# WIFIAdapter.net
KiCad netlist of a schematic drawn in EAGLE
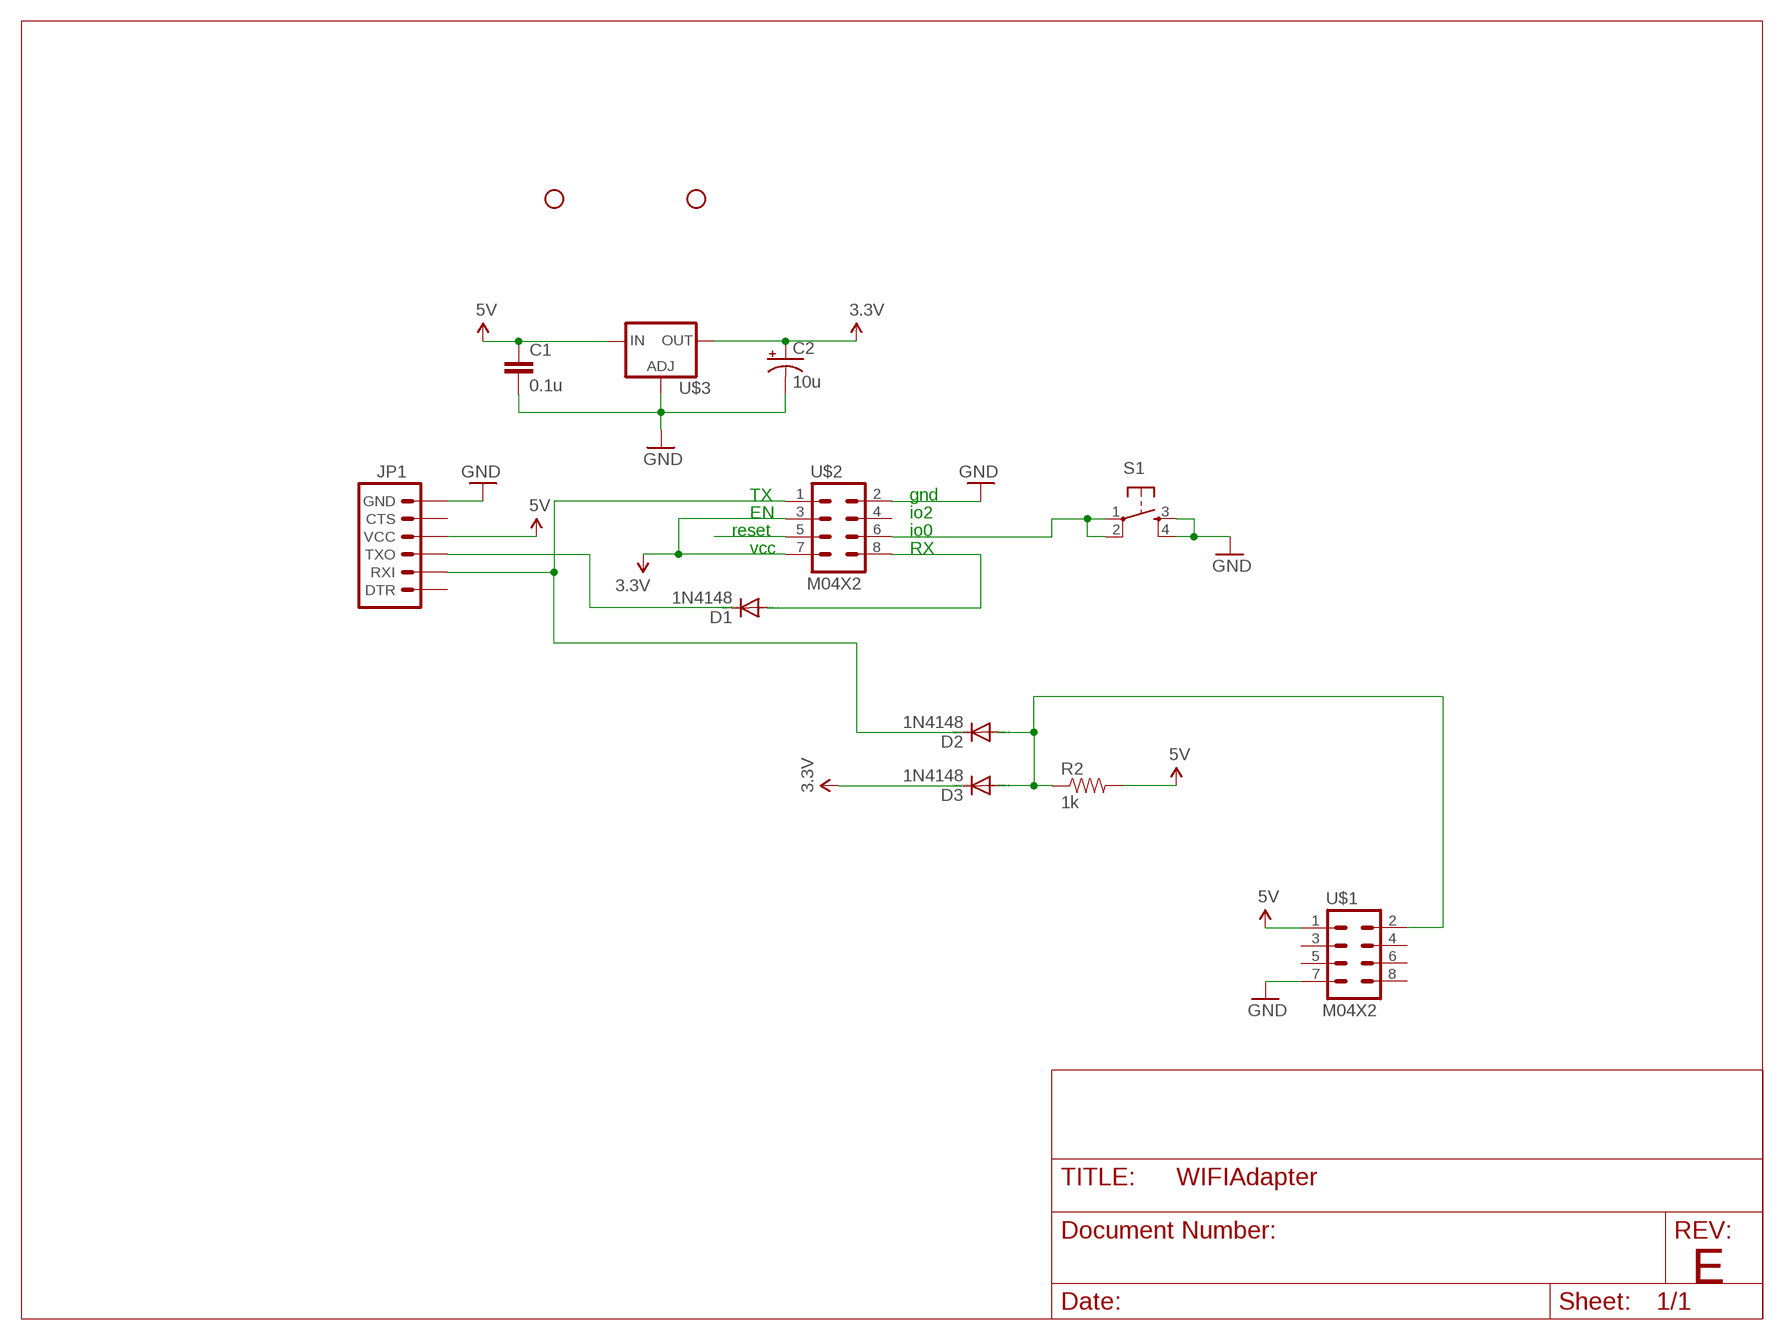
[diagram p0: schematic, sheet 1]

(export (version "E")
  (design (tool "Eeschema 10.0.6"))
  (components
    (comp (ref "C1")
      (value "0.1u")
      (footprint "eagle-import:CAP-PTH-SMALLEZ")
      (libsource (lib "eagle-import") (part "CAPEZ"))
    )
    (comp (ref "C2")
      (value "10u")
      (footprint "eagle-import:CPOL-RADIAL-10UF-25V")
      (libsource (lib "eagle-import") (part "CAP_POLPTH2"))
    )
    (comp (ref "D1")
      (value "1N4148")
      (footprint "eagle-import:DO35-7")
      (libsource (lib "eagle-import") (part "1N4148DO35-7"))
    )
    (comp (ref "D2")
      (value "1N4148")
      (footprint "eagle-import:DO35-7")
      (libsource (lib "eagle-import") (part "1N4148DO35-7"))
    )
    (comp (ref "D3")
      (value "1N4148")
      (footprint "eagle-import:DO35-7")
      (libsource (lib "eagle-import") (part "1N4148DO35-7"))
    )
    (comp (ref "JP1")
      (value "ARDUINO_SERIAL_PROGRAMLOCK")
      (footprint "eagle-import:1X06_LOCK")
      (libsource (lib "eagle-import") (part "ARDUINO_SERIAL_PROGRAMLOCK"))
    )
    (comp (ref "R2")
      (value "1k")
      (footprint "eagle-import:AXIAL-0.3EZ")
      (libsource (lib "eagle-import") (part "RESISTOREZ"))
    )
    (comp (ref "S1")
      (value "TAC_SWITCHPTH")
      (footprint "eagle-import:TACTILE-PTH")
      (libsource (lib "eagle-import") (part "TAC_SWITCHPTH"))
    )
    (comp (ref "STANDOFF1")
      (value "STAND-OFFTIGHT")
      (footprint "eagle-import:STAND-OFF-TIGHT")
      (libsource (lib "eagle-import") (part "STAND-OFFTIGHT"))
    )
    (comp (ref "STANDOFF2")
      (value "STAND-OFFTIGHT")
      (footprint "eagle-import:STAND-OFF-TIGHT")
      (libsource (lib "eagle-import") (part "STAND-OFFTIGHT"))
    )
    (comp (ref "U$1")
      (value "M04X2")
      (footprint "eagle-import:2X4")
      (libsource (lib "eagle-import") (part "M04X2"))
    )
    (comp (ref "U$2")
      (value "M04X2")
      (footprint "eagle-import:2X4")
      (libsource (lib "eagle-import") (part "M04X2"))
    )
    (comp (ref "U$3")
      (value "LM317TS")
      (footprint "eagle-import:317TS")
      (libsource (lib "eagle-import") (part "LM317TS"))
    )
  )
  (nets
    (net (code "1") (name "3.3V") (class "Default")
      (node (ref "C2") (pin "1") (pinfunction "+_1") (pintype "passive"))
      (node (ref "D3") (pin "C") (pinfunction "C_C") (pintype "passive"))
      (node (ref "U$2") (pin "3") (pinfunction "3_3") (pintype "passive"))
      (node (ref "U$2") (pin "7") (pinfunction "7_7") (pintype "passive"))
      (node (ref "U$3") (pin "2") (pinfunction "OUT_2") (pintype "passive"))
    )
    (net (code "2") (name "5V") (class "Default")
      (node (ref "C1") (pin "1") (pinfunction "1_1") (pintype "passive"))
      (node (ref "JP1") (pin "4") (pinfunction "VCC_4") (pintype "passive"))
      (node (ref "R2") (pin "P$2") (pinfunction "2_P$2") (pintype "passive"))
      (node (ref "U$1") (pin "1") (pinfunction "1_1") (pintype "passive"))
      (node (ref "U$3") (pin "3") (pinfunction "IN_3") (pintype "input"))
    )
    (net (code "3") (name "GND") (class "Default")
      (node (ref "C1") (pin "2") (pinfunction "2_2") (pintype "passive"))
      (node (ref "C2") (pin "2") (pinfunction "-_2") (pintype "passive"))
      (node (ref "JP1") (pin "6") (pinfunction "GND_6") (pintype "passive"))
      (node (ref "S1") (pin "3") (pinfunction "3_3") (pintype "passive"))
      (node (ref "S1") (pin "4") (pinfunction "4_4") (pintype "passive"))
      (node (ref "U$1") (pin "7") (pinfunction "7_7") (pintype "passive"))
      (node (ref "U$2") (pin "2") (pinfunction "2_2") (pintype "passive"))
      (node (ref "U$3") (pin "1") (pinfunction "ADJ_1") (pintype "input"))
    )
    (net (code "4") (name "Net-(D1-PadA)") (class "Default")
      (node (ref "D1") (pin "A") (pinfunction "A_A") (pintype "passive"))
      (node (ref "U$2") (pin "8") (pinfunction "8_8") (pintype "passive"))
    )
    (net (code "5") (name "Net-(JP1-RXI)") (class "Default")
      (node (ref "D2") (pin "C") (pinfunction "C_C") (pintype "passive"))
      (node (ref "JP1") (pin "2") (pinfunction "RXI_2") (pintype "passive"))
      (node (ref "U$2") (pin "1") (pinfunction "1_1") (pintype "passive"))
    )
    (net (code "6") (name "Net-(JP1-TXO)") (class "Default")
      (node (ref "D1") (pin "C") (pinfunction "C_C") (pintype "passive"))
      (node (ref "JP1") (pin "3") (pinfunction "TXO_3") (pintype "passive"))
    )
    (net (code "7") (name "Net-(R2-1)") (class "Default")
      (node (ref "D2") (pin "A") (pinfunction "A_A") (pintype "passive"))
      (node (ref "D3") (pin "A") (pinfunction "A_A") (pintype "passive"))
      (node (ref "R2") (pin "P$1") (pinfunction "1_P$1") (pintype "passive"))
      (node (ref "U$1") (pin "2") (pinfunction "2_2") (pintype "passive"))
    )
    (net (code "8") (name "Net-(S1-Pad1)") (class "Default")
      (node (ref "S1") (pin "1") (pinfunction "1_1") (pintype "passive"))
      (node (ref "S1") (pin "2") (pinfunction "2_2") (pintype "passive"))
      (node (ref "U$2") (pin "6") (pinfunction "6_6") (pintype "passive"))
    )
    (net (code "9") (name "unconnected-(JP1-CTS-Pad5)") (class "Default")
      (node (ref "JP1") (pin "5") (pinfunction "CTS_5") (pintype "passive"))
    )
    (net (code "10") (name "unconnected-(JP1-DTR-Pad1)") (class "Default")
      (node (ref "JP1") (pin "1") (pinfunction "DTR_1") (pintype "passive"))
    )
    (net (code "11") (name "unconnected-(U$1-Pad3)") (class "Default")
      (node (ref "U$1") (pin "3") (pinfunction "3_3") (pintype "passive"))
    )
    (net (code "12") (name "unconnected-(U$1-Pad4)") (class "Default")
      (node (ref "U$1") (pin "4") (pinfunction "4_4") (pintype "passive"))
    )
    (net (code "13") (name "unconnected-(U$1-Pad5)") (class "Default")
      (node (ref "U$1") (pin "5") (pinfunction "5_5") (pintype "passive"))
    )
    (net (code "14") (name "unconnected-(U$1-Pad6)") (class "Default")
      (node (ref "U$1") (pin "6") (pinfunction "6_6") (pintype "passive"))
    )
    (net (code "15") (name "unconnected-(U$1-Pad8)") (class "Default")
      (node (ref "U$1") (pin "8") (pinfunction "8_8") (pintype "passive"))
    )
    (net (code "16") (name "unconnected-(U$2-Pad4)") (class "Default")
      (node (ref "U$2") (pin "4") (pinfunction "4_4") (pintype "passive"))
    )
    (net (code "17") (name "unconnected-(U$2-Pad5)") (class "Default")
      (node (ref "U$2") (pin "5") (pinfunction "5_5") (pintype "passive"))
    )
  )
)
